# flash.net
KiCad netlist of a schematic drawn in Altium Designer
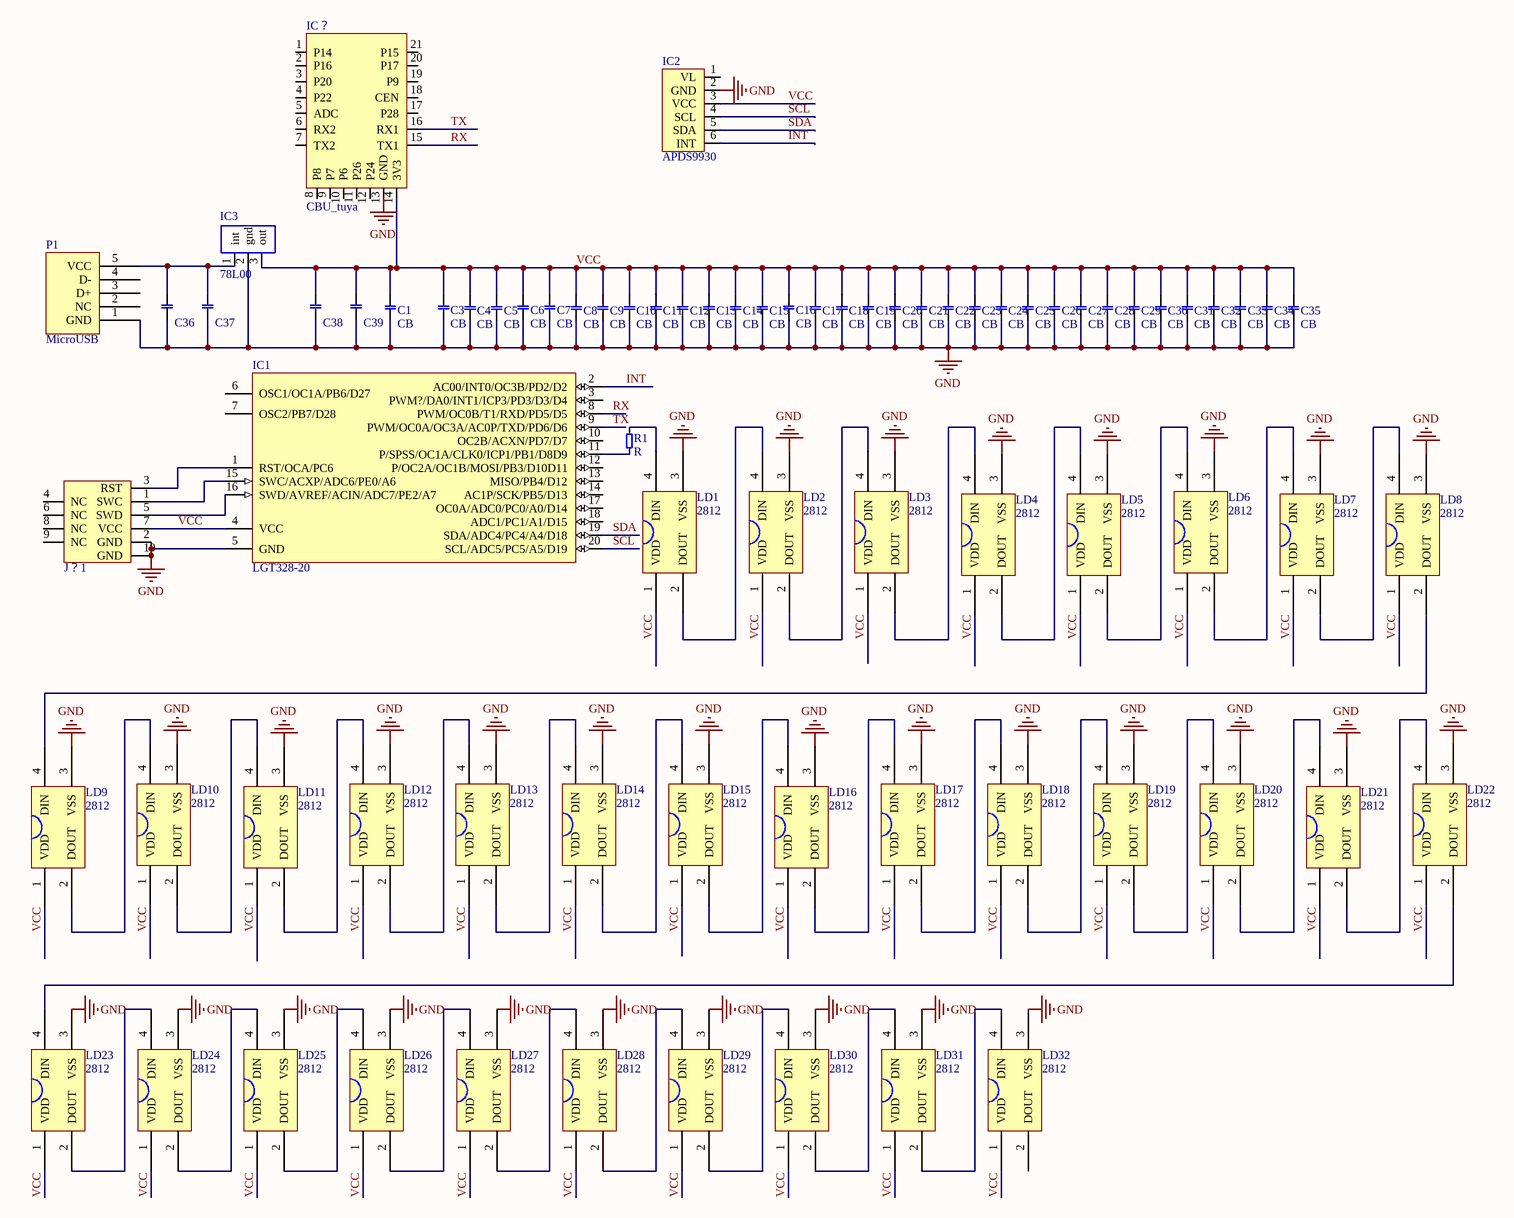
[diagram p0: flash.SchDoc]

(export (version "E")
  (design (tool "Eeschema 10.0.6"))
  (components
    (comp (ref "C1") (value "CB") (footprint "1206") (libsource (lib "MY") (part "CB")))
    (comp (ref "C3") (value "CB") (footprint "0805") (libsource (lib "MY") (part "CB")))
    (comp (ref "C4") (value "CB") (footprint "0805") (libsource (lib "MY") (part "CB")))
    (comp (ref "C5") (value "CB") (footprint "0805") (libsource (lib "MY") (part "CB")))
    (comp (ref "C6") (value "CB") (footprint "0805") (libsource (lib "MY") (part "CB")))
    (comp (ref "C7") (value "CB") (footprint "0805") (libsource (lib "MY") (part "CB")))
    (comp (ref "C8") (value "CB") (footprint "0805") (libsource (lib "MY") (part "CB")))
    (comp (ref "C9") (value "CB") (footprint "0805") (libsource (lib "MY") (part "CB")))
    (comp (ref "C10") (value "CB") (footprint "0805") (libsource (lib "MY") (part "CB")))
    (comp (ref "C11") (value "CB") (footprint "0805") (libsource (lib "MY") (part "CB")))
    (comp (ref "C12") (value "CB") (footprint "0805") (libsource (lib "MY") (part "CB")))
    (comp (ref "C13") (value "CB") (footprint "0805") (libsource (lib "MY") (part "CB")))
    (comp (ref "C14") (value "CB") (footprint "0805") (libsource (lib "MY") (part "CB")))
    (comp (ref "C15") (value "CB") (footprint "0805") (libsource (lib "MY") (part "CB")))
    (comp (ref "C16") (value "CB") (footprint "0805") (libsource (lib "MY") (part "CB")))
    (comp (ref "C17") (value "CB") (footprint "0805") (libsource (lib "MY") (part "CB")))
    (comp (ref "C18") (value "CB") (footprint "0805") (libsource (lib "MY") (part "CB")))
    (comp (ref "C19") (value "CB") (footprint "0805") (libsource (lib "MY") (part "CB")))
    (comp (ref "C20") (value "CB") (footprint "0805") (libsource (lib "MY") (part "CB")))
    (comp (ref "C21") (value "CB") (footprint "0805") (libsource (lib "MY") (part "CB")))
    (comp (ref "C22") (value "CB") (footprint "0805") (libsource (lib "MY") (part "CB")))
    (comp (ref "C23") (value "CB") (footprint "0805") (libsource (lib "MY") (part "CB")))
    (comp (ref "C24") (value "CB") (footprint "0805") (libsource (lib "MY") (part "CB")))
    (comp (ref "C25") (value "CB") (footprint "0805") (libsource (lib "MY") (part "CB")))
    (comp (ref "C26") (value "CB") (footprint "0805") (libsource (lib "MY") (part "CB")))
    (comp (ref "C27") (value "CB") (footprint "0805") (libsource (lib "MY") (part "CB")))
    (comp (ref "C28") (value "CB") (footprint "0805") (libsource (lib "MY") (part "CB")))
    (comp (ref "C29") (value "CB") (footprint "0805") (libsource (lib "MY") (part "CB")))
    (comp (ref "C30") (value "CB") (footprint "0805") (libsource (lib "MY") (part "CB")))
    (comp (ref "C31") (value "CB") (footprint "0805") (libsource (lib "MY") (part "CB")))
    (comp (ref "C32") (value "CB") (footprint "0805") (libsource (lib "MY") (part "CB")))
    (comp (ref "C33") (value "CB") (footprint "0805") (libsource (lib "MY") (part "CB")))
    (comp (ref "C34") (value "CB") (footprint "0805") (libsource (lib "MY") (part "CB")))
    (comp (ref "C35") (value "CB") (footprint "0805") (libsource (lib "MY") (part "CB")))
    (comp (ref "C36") (value "CB") (footprint "1206") (libsource (lib "MY") (part "CB")))
    (comp (ref "C37") (value "CB") (footprint "0805") (libsource (lib "MY") (part "CB")))
    (comp (ref "C38") (value "CB") (footprint "0805") (libsource (lib "MY") (part "CB")))
    (comp (ref "C39") (value "CB") (footprint "0805") (libsource (lib "MY") (part "CB")))
    (comp (ref "IC1") (value "LGT328-20") (footprint "LGT328-20") (libsource (lib "MY") (part "LGT328-20")))
    (comp (ref "IC2") (value "APDS9930") (footprint "APDS9930") (libsource (lib "MY") (part "APDS9930")))
    (comp (ref "IC3") (value "78L00") (footprint "SOT223") (libsource (lib "MY") (part "78L00")))
    (comp (ref "IC？") (value "CBU_tuya") (footprint "CBU_tuya") (libsource (lib "MY") (part "CBU_tuya")))
    (comp (ref "J？1") (value "LGTDOWN") (footprint "LGTDoWN-10") (libsource (lib "MY") (part "LGTDOWN-10")))
    (comp (ref "LD1") (value "2812") (footprint "WS2812") (libsource (lib "MY") (part "ws2812")))
    (comp (ref "LD2") (value "2812") (footprint "WS2812") (libsource (lib "MY") (part "ws2812")))
    (comp (ref "LD3") (value "2812") (footprint "WS2812") (libsource (lib "MY") (part "ws2812")))
    (comp (ref "LD4") (value "2812") (footprint "WS2812") (libsource (lib "MY") (part "ws2812")))
    (comp (ref "LD5") (value "2812") (footprint "WS2812") (libsource (lib "MY") (part "ws2812")))
    (comp (ref "LD6") (value "2812") (footprint "WS2812") (libsource (lib "MY") (part "ws2812")))
    (comp (ref "LD7") (value "2812") (footprint "WS2812") (libsource (lib "MY") (part "ws2812")))
    (comp (ref "LD8") (value "2812") (footprint "WS2812") (libsource (lib "MY") (part "ws2812")))
    (comp (ref "LD9") (value "2812") (footprint "WS2812") (libsource (lib "MY") (part "ws2812")))
    (comp (ref "LD10") (value "2812") (footprint "WS2812") (libsource (lib "MY") (part "ws2812")))
    (comp (ref "LD11") (value "2812") (footprint "WS2812") (libsource (lib "MY") (part "ws2812")))
    (comp (ref "LD12") (value "2812") (footprint "WS2812") (libsource (lib "MY") (part "ws2812")))
    (comp (ref "LD13") (value "2812") (footprint "WS2812") (libsource (lib "MY") (part "ws2812")))
    (comp (ref "LD14") (value "2812") (footprint "WS2812") (libsource (lib "MY") (part "ws2812")))
    (comp (ref "LD15") (value "2812") (footprint "WS2812") (libsource (lib "MY") (part "ws2812")))
    (comp (ref "LD16") (value "2812") (footprint "WS2812") (libsource (lib "MY") (part "ws2812")))
    (comp (ref "LD17") (value "2812") (footprint "WS2812") (libsource (lib "MY") (part "ws2812")))
    (comp (ref "LD18") (value "2812") (footprint "WS2812") (libsource (lib "MY") (part "ws2812")))
    (comp (ref "LD19") (value "2812") (footprint "WS2812") (libsource (lib "MY") (part "ws2812")))
    (comp (ref "LD20") (value "2812") (footprint "WS2812") (libsource (lib "MY") (part "ws2812")))
    (comp (ref "LD21") (value "2812") (footprint "WS2812") (libsource (lib "MY") (part "ws2812")))
    (comp (ref "LD22") (value "2812") (footprint "WS2812") (libsource (lib "MY") (part "ws2812")))
    (comp (ref "LD23") (value "2812") (footprint "WS2812") (libsource (lib "MY") (part "ws2812")))
    (comp (ref "LD24") (value "2812") (footprint "WS2812") (libsource (lib "MY") (part "ws2812")))
    (comp (ref "LD25") (value "2812") (footprint "WS2812") (libsource (lib "MY") (part "ws2812")))
    (comp (ref "LD26") (value "2812") (footprint "WS2812") (libsource (lib "MY") (part "ws2812")))
    (comp (ref "LD27") (value "2812") (footprint "WS2812") (libsource (lib "MY") (part "ws2812")))
    (comp (ref "LD28") (value "2812") (footprint "WS2812") (libsource (lib "MY") (part "ws2812")))
    (comp (ref "LD29") (value "2812") (footprint "WS2812") (libsource (lib "MY") (part "ws2812")))
    (comp (ref "LD30") (value "2812") (footprint "WS2812") (libsource (lib "MY") (part "ws2812")))
    (comp (ref "LD31") (value "2812") (footprint "WS2812") (libsource (lib "MY") (part "ws2812")))
    (comp (ref "LD32") (value "2812") (footprint "WS2812") (libsource (lib "MY") (part "ws2812")))
    (comp (ref "P1") (value "MicroUSB") (footprint "MicroUSB") (libsource (lib "MY") (part "MicroUSB")))
    (comp (ref "R1") (value "R") (footprint "0805") (libsource (lib "MY") (part "R")))
  )
  (nets
    (net (code "1") (name "/INT") (class "Default")
      (node (ref "IC1") (pin "2") (pinfunction "AC00/INT0/OC3B/PD2/D2_2") (pintype "bidirectional"))
      (node (ref "IC2") (pin "6") (pinfunction "INT_6") (pintype "passive"))
    )
    (net (code "2") (name "/RX") (class "Default")
      (node (ref "IC1") (pin "8") (pinfunction "PWM/OC0B/T1/RXD/PD5/D5_8") (pintype "bidirectional"))
      (node (ref "IC？") (pin "15") (pinfunction "TX1_15") (pintype "passive"))
    )
    (net (code "3") (name "/SCL") (class "Default")
      (node (ref "IC1") (pin "20") (pinfunction "SCL/ADC5/PC5/A5/D19_20") (pintype "bidirectional"))
      (node (ref "IC2") (pin "4") (pinfunction "SCL_4") (pintype "passive"))
    )
    (net (code "4") (name "/SDA") (class "Default")
      (node (ref "IC1") (pin "19") (pinfunction "SDA/ADC4/PC4/A4/D18_19") (pintype "bidirectional"))
      (node (ref "IC2") (pin "5") (pinfunction "SDA_5") (pintype "passive"))
    )
    (net (code "5") (name "/TX") (class "Default")
      (node (ref "IC1") (pin "9") (pinfunction "PWM/OC0A/OC3A/AC0P/TXD/PD6/D6_9") (pintype "bidirectional"))
      (node (ref "IC？") (pin "16") (pinfunction "RX1_16") (pintype "passive"))
    )
    (net (code "6") (name "/VCC") (class "Default")
      (node (ref "C1") (pin "1") (pintype "passive"))
      (node (ref "C10") (pin "1") (pintype "passive"))
      (node (ref "C11") (pin "1") (pintype "passive"))
      (node (ref "C12") (pin "1") (pintype "passive"))
      (node (ref "C13") (pin "1") (pintype "passive"))
      (node (ref "C14") (pin "1") (pintype "passive"))
      (node (ref "C15") (pin "1") (pintype "passive"))
      (node (ref "C16") (pin "1") (pintype "passive"))
      (node (ref "C17") (pin "1") (pintype "passive"))
      (node (ref "C18") (pin "1") (pintype "passive"))
      (node (ref "C19") (pin "1") (pintype "passive"))
      (node (ref "C20") (pin "1") (pintype "passive"))
      (node (ref "C21") (pin "1") (pintype "passive"))
      (node (ref "C22") (pin "1") (pintype "passive"))
      (node (ref "C23") (pin "1") (pintype "passive"))
      (node (ref "C24") (pin "1") (pintype "passive"))
      (node (ref "C25") (pin "1") (pintype "passive"))
      (node (ref "C26") (pin "1") (pintype "passive"))
      (node (ref "C27") (pin "1") (pintype "passive"))
      (node (ref "C28") (pin "1") (pintype "passive"))
      (node (ref "C29") (pin "1") (pintype "passive"))
      (node (ref "C3") (pin "1") (pintype "passive"))
      (node (ref "C30") (pin "1") (pintype "passive"))
      (node (ref "C31") (pin "1") (pintype "passive"))
      (node (ref "C32") (pin "1") (pintype "passive"))
      (node (ref "C33") (pin "1") (pintype "passive"))
      (node (ref "C34") (pin "1") (pintype "passive"))
      (node (ref "C35") (pin "1") (pintype "passive"))
      (node (ref "C38") (pin "1") (pintype "passive"))
      (node (ref "C39") (pin "1") (pintype "passive"))
      (node (ref "C4") (pin "1") (pintype "passive"))
      (node (ref "C5") (pin "1") (pintype "passive"))
      (node (ref "C6") (pin "1") (pintype "passive"))
      (node (ref "C7") (pin "1") (pintype "passive"))
      (node (ref "C8") (pin "1") (pintype "passive"))
      (node (ref "C9") (pin "1") (pintype "passive"))
      (node (ref "IC1") (pin "4") (pinfunction "VCC_4") (pintype "power_in"))
      (node (ref "IC2") (pin "3") (pinfunction "VCC_3") (pintype "passive"))
      (node (ref "IC3") (pin "3") (pinfunction "out_3") (pintype "bidirectional"))
      (node (ref "IC？") (pin "14") (pinfunction "3V3_14") (pintype "passive"))
      (node (ref "J？1") (pin "7") (pinfunction "VCC_7") (pintype "passive"))
      (node (ref "LD1") (pin "1") (pinfunction "VDD_1") (pintype "passive"))
      (node (ref "LD10") (pin "1") (pinfunction "VDD_1") (pintype "passive"))
      (node (ref "LD11") (pin "1") (pinfunction "VDD_1") (pintype "passive"))
      (node (ref "LD12") (pin "1") (pinfunction "VDD_1") (pintype "passive"))
      (node (ref "LD13") (pin "1") (pinfunction "VDD_1") (pintype "passive"))
      (node (ref "LD14") (pin "1") (pinfunction "VDD_1") (pintype "passive"))
      (node (ref "LD15") (pin "1") (pinfunction "VDD_1") (pintype "passive"))
      (node (ref "LD16") (pin "1") (pinfunction "VDD_1") (pintype "passive"))
      (node (ref "LD17") (pin "1") (pinfunction "VDD_1") (pintype "passive"))
      (node (ref "LD18") (pin "1") (pinfunction "VDD_1") (pintype "passive"))
      (node (ref "LD19") (pin "1") (pinfunction "VDD_1") (pintype "passive"))
      (node (ref "LD2") (pin "1") (pinfunction "VDD_1") (pintype "passive"))
      (node (ref "LD20") (pin "1") (pinfunction "VDD_1") (pintype "passive"))
      (node (ref "LD21") (pin "1") (pinfunction "VDD_1") (pintype "passive"))
      (node (ref "LD22") (pin "1") (pinfunction "VDD_1") (pintype "passive"))
      (node (ref "LD23") (pin "1") (pinfunction "VDD_1") (pintype "passive"))
      (node (ref "LD24") (pin "1") (pinfunction "VDD_1") (pintype "passive"))
      (node (ref "LD25") (pin "1") (pinfunction "VDD_1") (pintype "passive"))
      (node (ref "LD26") (pin "1") (pinfunction "VDD_1") (pintype "passive"))
      (node (ref "LD27") (pin "1") (pinfunction "VDD_1") (pintype "passive"))
      (node (ref "LD28") (pin "1") (pinfunction "VDD_1") (pintype "passive"))
      (node (ref "LD29") (pin "1") (pinfunction "VDD_1") (pintype "passive"))
      (node (ref "LD3") (pin "1") (pinfunction "VDD_1") (pintype "passive"))
      (node (ref "LD30") (pin "1") (pinfunction "VDD_1") (pintype "passive"))
      (node (ref "LD31") (pin "1") (pinfunction "VDD_1") (pintype "passive"))
      (node (ref "LD32") (pin "1") (pinfunction "VDD_1") (pintype "passive"))
      (node (ref "LD4") (pin "1") (pinfunction "VDD_1") (pintype "passive"))
      (node (ref "LD5") (pin "1") (pinfunction "VDD_1") (pintype "passive"))
      (node (ref "LD6") (pin "1") (pinfunction "VDD_1") (pintype "passive"))
      (node (ref "LD7") (pin "1") (pinfunction "VDD_1") (pintype "passive"))
      (node (ref "LD8") (pin "1") (pinfunction "VDD_1") (pintype "passive"))
      (node (ref "LD9") (pin "1") (pinfunction "VDD_1") (pintype "passive"))
    )
    (net (code "7") (name "GND") (class "Default")
      (node (ref "C1") (pin "2") (pintype "passive"))
      (node (ref "C10") (pin "2") (pintype "passive"))
      (node (ref "C11") (pin "2") (pintype "passive"))
      (node (ref "C12") (pin "2") (pintype "passive"))
      (node (ref "C13") (pin "2") (pintype "passive"))
      (node (ref "C14") (pin "2") (pintype "passive"))
      (node (ref "C15") (pin "2") (pintype "passive"))
      (node (ref "C16") (pin "2") (pintype "passive"))
      (node (ref "C17") (pin "2") (pintype "passive"))
      (node (ref "C18") (pin "2") (pintype "passive"))
      (node (ref "C19") (pin "2") (pintype "passive"))
      (node (ref "C20") (pin "2") (pintype "passive"))
      (node (ref "C21") (pin "2") (pintype "passive"))
      (node (ref "C22") (pin "2") (pintype "passive"))
      (node (ref "C23") (pin "2") (pintype "passive"))
      (node (ref "C24") (pin "2") (pintype "passive"))
      (node (ref "C25") (pin "2") (pintype "passive"))
      (node (ref "C26") (pin "2") (pintype "passive"))
      (node (ref "C27") (pin "2") (pintype "passive"))
      (node (ref "C28") (pin "2") (pintype "passive"))
      (node (ref "C29") (pin "2") (pintype "passive"))
      (node (ref "C3") (pin "2") (pintype "passive"))
      (node (ref "C30") (pin "2") (pintype "passive"))
      (node (ref "C31") (pin "2") (pintype "passive"))
      (node (ref "C32") (pin "2") (pintype "passive"))
      (node (ref "C33") (pin "2") (pintype "passive"))
      (node (ref "C34") (pin "2") (pintype "passive"))
      (node (ref "C35") (pin "2") (pintype "passive"))
      (node (ref "C36") (pin "2") (pintype "passive"))
      (node (ref "C37") (pin "2") (pintype "passive"))
      (node (ref "C38") (pin "2") (pintype "passive"))
      (node (ref "C39") (pin "2") (pintype "passive"))
      (node (ref "C4") (pin "2") (pintype "passive"))
      (node (ref "C5") (pin "2") (pintype "passive"))
      (node (ref "C6") (pin "2") (pintype "passive"))
      (node (ref "C7") (pin "2") (pintype "passive"))
      (node (ref "C8") (pin "2") (pintype "passive"))
      (node (ref "C9") (pin "2") (pintype "passive"))
      (node (ref "IC1") (pin "5") (pinfunction "GND_5") (pintype "power_in"))
      (node (ref "IC2") (pin "2") (pinfunction "GND_2") (pintype "passive"))
      (node (ref "IC3") (pin "2") (pinfunction "gnd_2") (pintype "bidirectional"))
      (node (ref "IC？") (pin "13") (pinfunction "GND_13") (pintype "passive"))
      (node (ref "J？1") (pin "10") (pinfunction "GND_10") (pintype "passive"))
      (node (ref "J？1") (pin "2") (pinfunction "GND_2") (pintype "passive"))
      (node (ref "LD1") (pin "3") (pinfunction "VSS_3") (pintype "passive"))
      (node (ref "LD10") (pin "3") (pinfunction "VSS_3") (pintype "passive"))
      (node (ref "LD11") (pin "3") (pinfunction "VSS_3") (pintype "passive"))
      (node (ref "LD12") (pin "3") (pinfunction "VSS_3") (pintype "passive"))
      (node (ref "LD13") (pin "3") (pinfunction "VSS_3") (pintype "passive"))
      (node (ref "LD14") (pin "3") (pinfunction "VSS_3") (pintype "passive"))
      (node (ref "LD15") (pin "3") (pinfunction "VSS_3") (pintype "passive"))
      (node (ref "LD16") (pin "3") (pinfunction "VSS_3") (pintype "passive"))
      (node (ref "LD17") (pin "3") (pinfunction "VSS_3") (pintype "passive"))
      (node (ref "LD18") (pin "3") (pinfunction "VSS_3") (pintype "passive"))
      (node (ref "LD19") (pin "3") (pinfunction "VSS_3") (pintype "passive"))
      (node (ref "LD2") (pin "3") (pinfunction "VSS_3") (pintype "passive"))
      (node (ref "LD20") (pin "3") (pinfunction "VSS_3") (pintype "passive"))
      (node (ref "LD21") (pin "3") (pinfunction "VSS_3") (pintype "passive"))
      (node (ref "LD22") (pin "3") (pinfunction "VSS_3") (pintype "passive"))
      (node (ref "LD23") (pin "3") (pinfunction "VSS_3") (pintype "passive"))
      (node (ref "LD24") (pin "3") (pinfunction "VSS_3") (pintype "passive"))
      (node (ref "LD25") (pin "3") (pinfunction "VSS_3") (pintype "passive"))
      (node (ref "LD26") (pin "3") (pinfunction "VSS_3") (pintype "passive"))
      (node (ref "LD27") (pin "3") (pinfunction "VSS_3") (pintype "passive"))
      (node (ref "LD28") (pin "3") (pinfunction "VSS_3") (pintype "passive"))
      (node (ref "LD29") (pin "3") (pinfunction "VSS_3") (pintype "passive"))
      (node (ref "LD3") (pin "3") (pinfunction "VSS_3") (pintype "passive"))
      (node (ref "LD30") (pin "3") (pinfunction "VSS_3") (pintype "passive"))
      (node (ref "LD31") (pin "3") (pinfunction "VSS_3") (pintype "passive"))
      (node (ref "LD32") (pin "3") (pinfunction "VSS_3") (pintype "passive"))
      (node (ref "LD4") (pin "3") (pinfunction "VSS_3") (pintype "passive"))
      (node (ref "LD5") (pin "3") (pinfunction "VSS_3") (pintype "passive"))
      (node (ref "LD6") (pin "3") (pinfunction "VSS_3") (pintype "passive"))
      (node (ref "LD7") (pin "3") (pinfunction "VSS_3") (pintype "passive"))
      (node (ref "LD8") (pin "3") (pinfunction "VSS_3") (pintype "passive"))
      (node (ref "LD9") (pin "3") (pinfunction "VSS_3") (pintype "passive"))
      (node (ref "P1") (pin "1") (pinfunction "GND_1") (pintype "passive"))
    )
    (net (code "8") (name "Net-(IC1-P{slash}SPSS{slash}OC1A{slash}CLK0{slash}ICP1{slash}PB1{slash}D8D9)") (class "Default")
      (node (ref "IC1") (pin "11") (pinfunction "P/SPSS/OC1A/CLK0/ICP1/PB1/D8D9_11") (pintype "bidirectional"))
      (node (ref "R1") (pin "1") (pinfunction "1_1") (pintype "passive"))
    )
    (net (code "9") (name "Net-(IC1-RST{slash}OCA{slash}PC6)") (class "Default")
      (node (ref "IC1") (pin "1") (pinfunction "RST/OCA/PC6_1") (pintype "power_in"))
      (node (ref "J？1") (pin "3") (pinfunction "RST_3") (pintype "passive"))
    )
    (net (code "10") (name "Net-(IC1-SWC{slash}ACXP{slash}ADC6{slash}PE0{slash}A6)") (class "Default")
      (node (ref "IC1") (pin "15") (pinfunction "SWC/ACXP/ADC6/PE0/A6_15") (pintype "input"))
      (node (ref "J？1") (pin "1") (pinfunction "SWC_1") (pintype "passive"))
    )
    (net (code "11") (name "Net-(IC1-SWD{slash}AVREF{slash}ACIN{slash}ADC7{slash}PE2{slash}A7)") (class "Default")
      (node (ref "IC1") (pin "16") (pinfunction "SWD/AVREF/ACIN/ADC7/PE2/A7_16") (pintype "input"))
      (node (ref "J？1") (pin "5") (pinfunction "SWD_5") (pintype "passive"))
    )
    (net (code "12") (name "Net-(IC3-int)") (class "Default")
      (node (ref "C36") (pin "1") (pintype "passive"))
      (node (ref "C37") (pin "1") (pintype "passive"))
      (node (ref "IC3") (pin "1") (pinfunction "int_1") (pintype "bidirectional"))
      (node (ref "P1") (pin "5") (pinfunction "VCC_5") (pintype "passive"))
    )
    (net (code "13") (name "Net-(LD1-DIN)") (class "Default")
      (node (ref "LD1") (pin "4") (pinfunction "DIN_4") (pintype "passive"))
      (node (ref "R1") (pin "2") (pinfunction "2_2") (pintype "passive"))
    )
    (net (code "14") (name "Net-(LD1-DOUT)") (class "Default")
      (node (ref "LD1") (pin "2") (pinfunction "DOUT_2") (pintype "passive"))
      (node (ref "LD2") (pin "4") (pinfunction "DIN_4") (pintype "passive"))
    )
    (net (code "15") (name "Net-(LD2-DOUT)") (class "Default")
      (node (ref "LD2") (pin "2") (pinfunction "DOUT_2") (pintype "passive"))
      (node (ref "LD3") (pin "4") (pinfunction "DIN_4") (pintype "passive"))
    )
    (net (code "16") (name "Net-(LD3-DOUT)") (class "Default")
      (node (ref "LD3") (pin "2") (pinfunction "DOUT_2") (pintype "passive"))
      (node (ref "LD4") (pin "4") (pinfunction "DIN_4") (pintype "passive"))
    )
    (net (code "17") (name "Net-(LD4-DOUT)") (class "Default")
      (node (ref "LD4") (pin "2") (pinfunction "DOUT_2") (pintype "passive"))
      (node (ref "LD5") (pin "4") (pinfunction "DIN_4") (pintype "passive"))
    )
    (net (code "18") (name "Net-(LD5-DOUT)") (class "Default")
      (node (ref "LD5") (pin "2") (pinfunction "DOUT_2") (pintype "passive"))
      (node (ref "LD6") (pin "4") (pinfunction "DIN_4") (pintype "passive"))
    )
    (net (code "19") (name "Net-(LD6-DOUT)") (class "Default")
      (node (ref "LD6") (pin "2") (pinfunction "DOUT_2") (pintype "passive"))
      (node (ref "LD7") (pin "4") (pinfunction "DIN_4") (pintype "passive"))
    )
    (net (code "20") (name "Net-(LD7-DOUT)") (class "Default")
      (node (ref "LD7") (pin "2") (pinfunction "DOUT_2") (pintype "passive"))
      (node (ref "LD8") (pin "4") (pinfunction "DIN_4") (pintype "passive"))
    )
    (net (code "21") (name "Net-(LD8-DOUT)") (class "Default")
      (node (ref "LD8") (pin "2") (pinfunction "DOUT_2") (pintype "passive"))
      (node (ref "LD9") (pin "4") (pinfunction "DIN_4") (pintype "passive"))
    )
    (net (code "22") (name "Net-(LD10-DIN)") (class "Default")
      (node (ref "LD10") (pin "4") (pinfunction "DIN_4") (pintype "passive"))
      (node (ref "LD9") (pin "2") (pinfunction "DOUT_2") (pintype "passive"))
    )
    (net (code "23") (name "Net-(LD10-DOUT)") (class "Default")
      (node (ref "LD10") (pin "2") (pinfunction "DOUT_2") (pintype "passive"))
      (node (ref "LD11") (pin "4") (pinfunction "DIN_4") (pintype "passive"))
    )
    (net (code "24") (name "Net-(LD11-DOUT)") (class "Default")
      (node (ref "LD11") (pin "2") (pinfunction "DOUT_2") (pintype "passive"))
      (node (ref "LD12") (pin "4") (pinfunction "DIN_4") (pintype "passive"))
    )
    (net (code "25") (name "Net-(LD12-DOUT)") (class "Default")
      (node (ref "LD12") (pin "2") (pinfunction "DOUT_2") (pintype "passive"))
      (node (ref "LD13") (pin "4") (pinfunction "DIN_4") (pintype "passive"))
    )
    (net (code "26") (name "Net-(LD13-DOUT)") (class "Default")
      (node (ref "LD13") (pin "2") (pinfunction "DOUT_2") (pintype "passive"))
      (node (ref "LD14") (pin "4") (pinfunction "DIN_4") (pintype "passive"))
    )
    (net (code "27") (name "Net-(LD14-DOUT)") (class "Default")
      (node (ref "LD14") (pin "2") (pinfunction "DOUT_2") (pintype "passive"))
      (node (ref "LD15") (pin "4") (pinfunction "DIN_4") (pintype "passive"))
    )
    (net (code "28") (name "Net-(LD15-DOUT)") (class "Default")
      (node (ref "LD15") (pin "2") (pinfunction "DOUT_2") (pintype "passive"))
      (node (ref "LD16") (pin "4") (pinfunction "DIN_4") (pintype "passive"))
    )
    (net (code "29") (name "Net-(LD16-DOUT)") (class "Default")
      (node (ref "LD16") (pin "2") (pinfunction "DOUT_2") (pintype "passive"))
      (node (ref "LD17") (pin "4") (pinfunction "DIN_4") (pintype "passive"))
    )
    (net (code "30") (name "Net-(LD17-DOUT)") (class "Default")
      (node (ref "LD17") (pin "2") (pinfunction "DOUT_2") (pintype "passive"))
      (node (ref "LD18") (pin "4") (pinfunction "DIN_4") (pintype "passive"))
    )
    (net (code "31") (name "Net-(LD18-DOUT)") (class "Default")
      (node (ref "LD18") (pin "2") (pinfunction "DOUT_2") (pintype "passive"))
      (node (ref "LD19") (pin "4") (pinfunction "DIN_4") (pintype "passive"))
    )
    (net (code "32") (name "Net-(LD19-DOUT)") (class "Default")
      (node (ref "LD19") (pin "2") (pinfunction "DOUT_2") (pintype "passive"))
      (node (ref "LD20") (pin "4") (pinfunction "DIN_4") (pintype "passive"))
    )
    (net (code "33") (name "Net-(LD20-DOUT)") (class "Default")
      (node (ref "LD20") (pin "2") (pinfunction "DOUT_2") (pintype "passive"))
      (node (ref "LD21") (pin "4") (pinfunction "DIN_4") (pintype "passive"))
    )
    (net (code "34") (name "Net-(LD21-DOUT)") (class "Default")
      (node (ref "LD21") (pin "2") (pinfunction "DOUT_2") (pintype "passive"))
      (node (ref "LD22") (pin "4") (pinfunction "DIN_4") (pintype "passive"))
    )
    (net (code "35") (name "Net-(LD22-DOUT)") (class "Default")
      (node (ref "LD22") (pin "2") (pinfunction "DOUT_2") (pintype "passive"))
      (node (ref "LD23") (pin "4") (pinfunction "DIN_4") (pintype "passive"))
    )
    (net (code "36") (name "Net-(LD23-DOUT)") (class "Default")
      (node (ref "LD23") (pin "2") (pinfunction "DOUT_2") (pintype "passive"))
      (node (ref "LD24") (pin "4") (pinfunction "DIN_4") (pintype "passive"))
    )
    (net (code "37") (name "Net-(LD24-DOUT)") (class "Default")
      (node (ref "LD24") (pin "2") (pinfunction "DOUT_2") (pintype "passive"))
      (node (ref "LD25") (pin "4") (pinfunction "DIN_4") (pintype "passive"))
    )
    (net (code "38") (name "Net-(LD25-DOUT)") (class "Default")
      (node (ref "LD25") (pin "2") (pinfunction "DOUT_2") (pintype "passive"))
      (node (ref "LD26") (pin "4") (pinfunction "DIN_4") (pintype "passive"))
    )
    (net (code "39") (name "Net-(LD26-DOUT)") (class "Default")
      (node (ref "LD26") (pin "2") (pinfunction "DOUT_2") (pintype "passive"))
      (node (ref "LD27") (pin "4") (pinfunction "DIN_4") (pintype "passive"))
    )
    (net (code "40") (name "Net-(LD27-DOUT)") (class "Default")
      (node (ref "LD27") (pin "2") (pinfunction "DOUT_2") (pintype "passive"))
      (node (ref "LD28") (pin "4") (pinfunction "DIN_4") (pintype "passive"))
    )
    (net (code "41") (name "Net-(LD28-DOUT)") (class "Default")
      (node (ref "LD28") (pin "2") (pinfunction "DOUT_2") (pintype "passive"))
      (node (ref "LD29") (pin "4") (pinfunction "DIN_4") (pintype "passive"))
    )
    (net (code "42") (name "Net-(LD29-DOUT)") (class "Default")
      (node (ref "LD29") (pin "2") (pinfunction "DOUT_2") (pintype "passive"))
      (node (ref "LD30") (pin "4") (pinfunction "DIN_4") (pintype "passive"))
    )
    (net (code "43") (name "Net-(LD30-DOUT)") (class "Default")
      (node (ref "LD30") (pin "2") (pinfunction "DOUT_2") (pintype "passive"))
      (node (ref "LD31") (pin "4") (pinfunction "DIN_4") (pintype "passive"))
    )
    (net (code "44") (name "Net-(LD31-DOUT)") (class "Default")
      (node (ref "LD31") (pin "2") (pinfunction "DOUT_2") (pintype "passive"))
      (node (ref "LD32") (pin "4") (pinfunction "DIN_4") (pintype "passive"))
    )
    (net (code "45") (name "unconnected-(IC1-AC1P{slash}SCK{slash}PB5{slash}D13-Pad14)") (class "Default")
      (node (ref "IC1") (pin "14") (pinfunction "AC1P/SCK/PB5/D13_14") (pintype "bidirectional"))
    )
    (net (code "46") (name "unconnected-(IC1-ADC1{slash}PC1{slash}A1{slash}D15-Pad18)") (class "Default")
      (node (ref "IC1") (pin "18") (pinfunction "ADC1/PC1/A1/D15_18") (pintype "bidirectional"))
    )
    (net (code "47") (name "unconnected-(IC1-MISO{slash}PB4{slash}D12-Pad13)") (class "Default")
      (node (ref "IC1") (pin "13") (pinfunction "MISO/PB4/D12_13") (pintype "bidirectional"))
    )
    (net (code "48") (name "unconnected-(IC1-OC0A{slash}ADC0{slash}PC0{slash}A0{slash}D14-Pad17)") (class "Default")
      (node (ref "IC1") (pin "17") (pinfunction "OC0A/ADC0/PC0/A0/D14_17") (pintype "bidirectional"))
    )
    (net (code "49") (name "unconnected-(IC1-OC2B{slash}ACXN{slash}PD7{slash}D7-Pad10)") (class "Default")
      (node (ref "IC1") (pin "10") (pinfunction "OC2B/ACXN/PD7/D7_10") (pintype "bidirectional"))
    )
    (net (code "50") (name "unconnected-(IC1-OSC1{slash}OC1A{slash}PB6{slash}D27-Pad6)") (class "Default")
      (node (ref "IC1") (pin "6") (pinfunction "OSC1/OC1A/PB6/D27_6") (pintype "passive"))
    )
    (net (code "51") (name "unconnected-(IC1-OSC2{slash}PB7{slash}D28-Pad7)") (class "Default")
      (node (ref "IC1") (pin "7") (pinfunction "OSC2/PB7/D28_7") (pintype "passive"))
    )
    (net (code "52") (name "unconnected-(IC1-PWM?{slash}DA0{slash}INT1{slash}ICP3{slash}PD3{slash}D3{slash}D4-Pad3)") (class "Default")
      (node (ref "IC1") (pin "3") (pinfunction "PWM?/DA0/INT1/ICP3/PD3/D3/D4_3") (pintype "bidirectional"))
    )
    (net (code "53") (name "unconnected-(IC1-P{slash}OC2A{slash}OC1B{slash}MOSI{slash}PB3{slash}D10D11-Pad12)") (class "Default")
      (node (ref "IC1") (pin "12") (pinfunction "P/OC2A/OC1B/MOSI/PB3/D10D11_12") (pintype "bidirectional"))
    )
    (net (code "54") (name "unconnected-(IC2-VL-Pad1)") (class "Default")
      (node (ref "IC2") (pin "1") (pinfunction "VL_1") (pintype "passive"))
    )
    (net (code "55") (name "unconnected-(IC？-ADC-Pad5)") (class "Default")
      (node (ref "IC？") (pin "5") (pinfunction "ADC_5") (pintype "passive"))
    )
    (net (code "56") (name "unconnected-(IC？-CEN-Pad18)") (class "Default")
      (node (ref "IC？") (pin "18") (pinfunction "CEN_18") (pintype "passive"))
    )
    (net (code "57") (name "unconnected-(IC？-P6-Pad10)") (class "Default")
      (node (ref "IC？") (pin "10") (pinfunction "P6_10") (pintype "passive"))
    )
    (net (code "58") (name "unconnected-(IC？-P7-Pad9)") (class "Default")
      (node (ref "IC？") (pin "9") (pinfunction "P7_9") (pintype "passive"))
    )
    (net (code "59") (name "unconnected-(IC？-P8-Pad8)") (class "Default")
      (node (ref "IC？") (pin "8") (pinfunction "P8_8") (pintype "passive"))
    )
    (net (code "60") (name "unconnected-(IC？-P9-Pad19)") (class "Default")
      (node (ref "IC？") (pin "19") (pinfunction "P9_19") (pintype "passive"))
    )
    (net (code "61") (name "unconnected-(IC？-P14-Pad1)") (class "Default")
      (node (ref "IC？") (pin "1") (pinfunction "P14_1") (pintype "passive"))
    )
    (net (code "62") (name "unconnected-(IC？-P15-Pad21)") (class "Default")
      (node (ref "IC？") (pin "21") (pinfunction "P15_21") (pintype "passive"))
    )
    (net (code "63") (name "unconnected-(IC？-P16-Pad2)") (class "Default")
      (node (ref "IC？") (pin "2") (pinfunction "P16_2") (pintype "passive"))
    )
    (net (code "64") (name "unconnected-(IC？-P17-Pad20)") (class "Default")
      (node (ref "IC？") (pin "20") (pinfunction "P17_20") (pintype "passive"))
    )
    (net (code "65") (name "unconnected-(IC？-P20-Pad3)") (class "Default")
      (node (ref "IC？") (pin "3") (pinfunction "P20_3") (pintype "passive"))
    )
    (net (code "66") (name "unconnected-(IC？-P22-Pad4)") (class "Default")
      (node (ref "IC？") (pin "4") (pinfunction "P22_4") (pintype "passive"))
    )
    (net (code "67") (name "unconnected-(IC？-P24-Pad12)") (class "Default")
      (node (ref "IC？") (pin "12") (pinfunction "P24_12") (pintype "passive"))
    )
    (net (code "68") (name "unconnected-(IC？-P26-Pad11)") (class "Default")
      (node (ref "IC？") (pin "11") (pinfunction "P26_11") (pintype "passive"))
    )
    (net (code "69") (name "unconnected-(IC？-P28-Pad17)") (class "Default")
      (node (ref "IC？") (pin "17") (pinfunction "P28_17") (pintype "passive"))
    )
    (net (code "70") (name "unconnected-(IC？-RX2-Pad6)") (class "Default")
      (node (ref "IC？") (pin "6") (pinfunction "RX2_6") (pintype "passive"))
    )
    (net (code "71") (name "unconnected-(IC？-TX2-Pad7)") (class "Default")
      (node (ref "IC？") (pin "7") (pinfunction "TX2_7") (pintype "passive"))
    )
    (net (code "72") (name "unconnected-(J？1-NC-Pad4)") (class "Default")
      (node (ref "J？1") (pin "4") (pinfunction "NC_4") (pintype "passive"))
    )
    (net (code "73") (name "unconnected-(J？1-NC-Pad6)") (class "Default")
      (node (ref "J？1") (pin "6") (pinfunction "NC_6") (pintype "passive"))
    )
    (net (code "74") (name "unconnected-(J？1-NC-Pad8)") (class "Default")
      (node (ref "J？1") (pin "8") (pinfunction "NC_8") (pintype "passive"))
    )
    (net (code "75") (name "unconnected-(J？1-NC-Pad9)") (class "Default")
      (node (ref "J？1") (pin "9") (pinfunction "NC_9") (pintype "passive"))
    )
    (net (code "76") (name "unconnected-(LD32-DOUT-Pad2)") (class "Default")
      (node (ref "LD32") (pin "2") (pinfunction "DOUT_2") (pintype "passive"))
    )
    (net (code "77") (name "unconnected-(P1-D+-Pad3)") (class "Default")
      (node (ref "P1") (pin "3") (pinfunction "D+_3") (pintype "passive"))
    )
    (net (code "78") (name "unconnected-(P1-D--Pad4)") (class "Default")
      (node (ref "P1") (pin "4") (pinfunction "D-_4") (pintype "passive"))
    )
    (net (code "79") (name "unconnected-(P1-NC-Pad2)") (class "Default")
      (node (ref "P1") (pin "2") (pinfunction "NC_2") (pintype "passive"))
    )
  )
)
